# SDRAM.net
KiCad netlist of a schematic drawn in Altium Designer
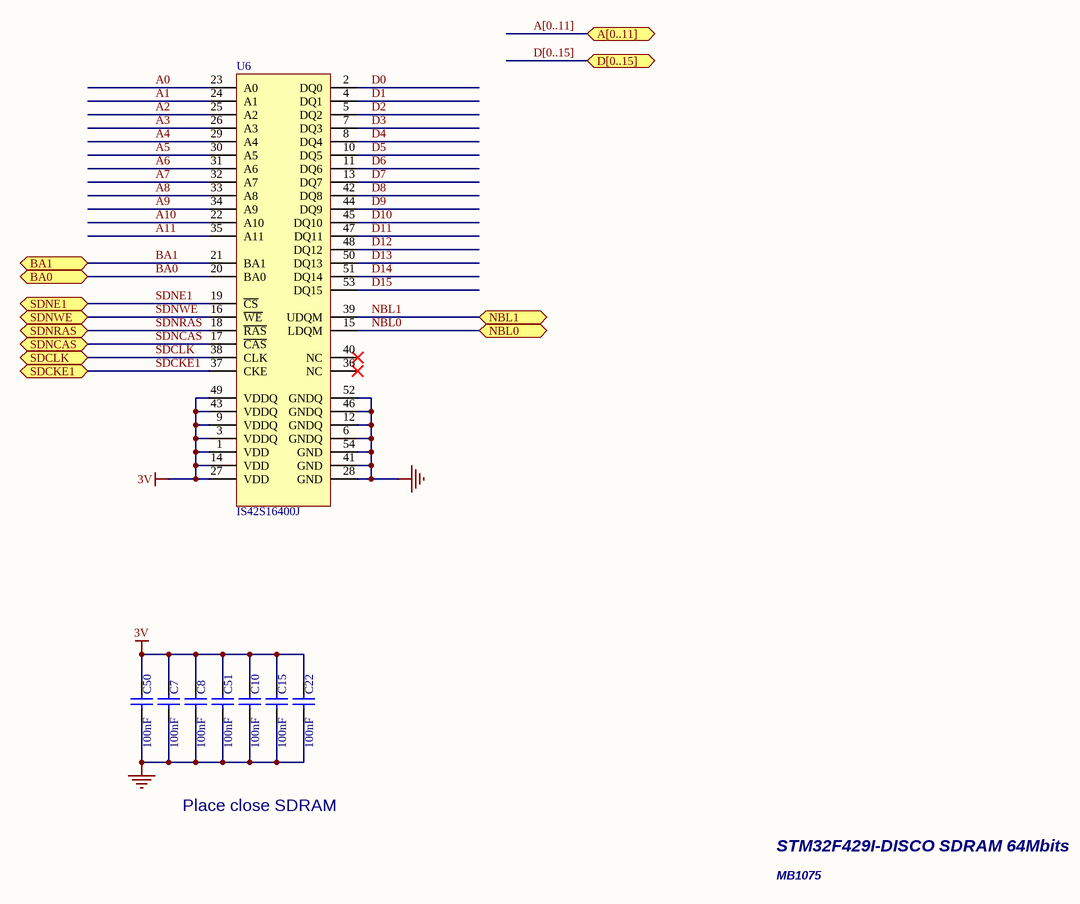
[diagram p0: SDRAM.SchDoc]

(export (version "E")
  (design (tool "Eeschema 10.0.6"))
  (components
    (comp (ref "C7")
      (value "100nF")
      (footprint "0402C")
      (description "Capacitor 0402 / 0603 / 0805")
      (libsource (lib "MCD_TOOLS") (part "Capacitor_ST"))
    )
    (comp (ref "C8")
      (value "100nF")
      (footprint "0402C")
      (description "Capacitor 0402 / 0603 / 0805")
      (libsource (lib "MCD_TOOLS") (part "Capacitor_ST"))
    )
    (comp (ref "C10")
      (value "100nF")
      (footprint "0402C")
      (description "Capacitor 0402 / 0603 / 0805")
      (libsource (lib "MCD_TOOLS") (part "Capacitor_ST"))
    )
    (comp (ref "C15")
      (value "100nF")
      (footprint "0402C")
      (description "Capacitor 0402 / 0603 / 0805")
      (libsource (lib "MCD_TOOLS") (part "Capacitor_ST"))
    )
    (comp (ref "C22")
      (value "100nF")
      (footprint "0402C")
      (description "Capacitor 0402 / 0603 / 0805")
      (libsource (lib "MCD_TOOLS") (part "Capacitor_ST"))
    )
    (comp (ref "C50")
      (value "100nF")
      (footprint "0402C")
      (description "Capacitor 0402 / 0603 / 0805")
      (libsource (lib "MCD_TOOLS") (part "Capacitor_ST"))
    )
    (comp (ref "C51")
      (value "100nF")
      (footprint "0402C")
      (description "Capacitor 0402 / 0603 / 0805")
      (libsource (lib "MCD_TOOLS") (part "Capacitor_ST"))
    )
    (comp (ref "U6")
      (value "IS42S16400J")
      (footprint "TSOP54-II")
      (description "SYNCHRONOUS DYNAMIC RAM, 1 Meg Bits x 16 Bits x 4 Banks (64-MBIT)")
      (libsource (lib "MCD_TOOLS") (part "IS45S16400J"))
    )
  )
  (nets
    (net (code "1") (name "/A0") (class "Default")
      (node (ref "U6") (pin "23") (pinfunction "A0_23") (pintype "passive"))
    )
    (net (code "2") (name "/A1") (class "Default")
      (node (ref "U6") (pin "24") (pinfunction "A1_24") (pintype "passive"))
    )
    (net (code "3") (name "/A2") (class "Default")
      (node (ref "U6") (pin "25") (pinfunction "A2_25") (pintype "passive"))
    )
    (net (code "4") (name "/A3") (class "Default")
      (node (ref "U6") (pin "26") (pinfunction "A3_26") (pintype "passive"))
    )
    (net (code "5") (name "/A4") (class "Default")
      (node (ref "U6") (pin "29") (pinfunction "A4_29") (pintype "passive"))
    )
    (net (code "6") (name "/A5") (class "Default")
      (node (ref "U6") (pin "30") (pinfunction "A5_30") (pintype "passive"))
    )
    (net (code "7") (name "/A6") (class "Default")
      (node (ref "U6") (pin "31") (pinfunction "A6_31") (pintype "passive"))
    )
    (net (code "8") (name "/A7") (class "Default")
      (node (ref "U6") (pin "32") (pinfunction "A7_32") (pintype "passive"))
    )
    (net (code "9") (name "/A8") (class "Default")
      (node (ref "U6") (pin "33") (pinfunction "A8_33") (pintype "passive"))
    )
    (net (code "10") (name "/A9") (class "Default")
      (node (ref "U6") (pin "34") (pinfunction "A9_34") (pintype "passive"))
    )
    (net (code "11") (name "/A10") (class "Default")
      (node (ref "U6") (pin "22") (pinfunction "A10_22") (pintype "passive"))
    )
    (net (code "12") (name "/A11") (class "Default")
      (node (ref "U6") (pin "35") (pinfunction "A11_35") (pintype "passive"))
    )
    (net (code "14") (name "/BA0") (class "Default")
      (node (ref "U6") (pin "20") (pinfunction "BA0_20") (pintype "passive"))
    )
    (net (code "15") (name "/BA1") (class "Default")
      (node (ref "U6") (pin "21") (pinfunction "BA1_21") (pintype "passive"))
    )
    (net (code "16") (name "/D0") (class "Default")
      (node (ref "U6") (pin "2") (pinfunction "DQ0_2") (pintype "passive"))
    )
    (net (code "17") (name "/D1") (class "Default")
      (node (ref "U6") (pin "4") (pinfunction "DQ1_4") (pintype "passive"))
    )
    (net (code "18") (name "/D2") (class "Default")
      (node (ref "U6") (pin "5") (pinfunction "DQ2_5") (pintype "passive"))
    )
    (net (code "19") (name "/D3") (class "Default")
      (node (ref "U6") (pin "7") (pinfunction "DQ3_7") (pintype "passive"))
    )
    (net (code "20") (name "/D4") (class "Default")
      (node (ref "U6") (pin "8") (pinfunction "DQ4_8") (pintype "passive"))
    )
    (net (code "21") (name "/D5") (class "Default")
      (node (ref "U6") (pin "10") (pinfunction "DQ5_10") (pintype "passive"))
    )
    (net (code "22") (name "/D6") (class "Default")
      (node (ref "U6") (pin "11") (pinfunction "DQ6_11") (pintype "passive"))
    )
    (net (code "23") (name "/D7") (class "Default")
      (node (ref "U6") (pin "13") (pinfunction "DQ7_13") (pintype "passive"))
    )
    (net (code "24") (name "/D8") (class "Default")
      (node (ref "U6") (pin "42") (pinfunction "DQ8_42") (pintype "passive"))
    )
    (net (code "25") (name "/D9") (class "Default")
      (node (ref "U6") (pin "44") (pinfunction "DQ9_44") (pintype "passive"))
    )
    (net (code "26") (name "/D10") (class "Default")
      (node (ref "U6") (pin "45") (pinfunction "DQ10_45") (pintype "passive"))
    )
    (net (code "27") (name "/D11") (class "Default")
      (node (ref "U6") (pin "47") (pinfunction "DQ11_47") (pintype "passive"))
    )
    (net (code "28") (name "/D12") (class "Default")
      (node (ref "U6") (pin "48") (pinfunction "DQ12_48") (pintype "passive"))
    )
    (net (code "29") (name "/D13") (class "Default")
      (node (ref "U6") (pin "50") (pinfunction "DQ13_50") (pintype "passive"))
    )
    (net (code "30") (name "/D14") (class "Default")
      (node (ref "U6") (pin "51") (pinfunction "DQ14_51") (pintype "passive"))
    )
    (net (code "31") (name "/D15") (class "Default")
      (node (ref "U6") (pin "53") (pinfunction "DQ15_53") (pintype "passive"))
    )
    (net (code "33") (name "/NBL0") (class "Default")
      (node (ref "U6") (pin "15") (pinfunction "LDQM_15") (pintype "passive"))
    )
    (net (code "34") (name "/NBL1") (class "Default")
      (node (ref "U6") (pin "39") (pinfunction "UDQM_39") (pintype "passive"))
    )
    (net (code "35") (name "/SDCKE1") (class "Default")
      (node (ref "U6") (pin "37") (pinfunction "CKE_37") (pintype "passive"))
    )
    (net (code "36") (name "/SDCLK") (class "Default")
      (node (ref "U6") (pin "38") (pinfunction "CLK_38") (pintype "passive"))
    )
    (net (code "37") (name "/SDNCAS") (class "Default")
      (node (ref "U6") (pin "17") (pinfunction "~{CAS}_17") (pintype "passive"))
    )
    (net (code "38") (name "/SDNE1") (class "Default")
      (node (ref "U6") (pin "19") (pinfunction "~{CS}_19") (pintype "passive"))
    )
    (net (code "39") (name "/SDNRAS") (class "Default")
      (node (ref "U6") (pin "18") (pinfunction "~{RAS}_18") (pintype "passive"))
    )
    (net (code "40") (name "/SDNWE") (class "Default")
      (node (ref "U6") (pin "16") (pinfunction "~{WE}_16") (pintype "passive"))
    )
    (net (code "41") (name "3V") (class "Default")
      (node (ref "C10") (pin "2") (pinfunction "2_2") (pintype "passive"))
      (node (ref "C15") (pin "2") (pinfunction "2_2") (pintype "passive"))
      (node (ref "C22") (pin "2") (pinfunction "2_2") (pintype "passive"))
      (node (ref "C50") (pin "2") (pinfunction "2_2") (pintype "passive"))
      (node (ref "C51") (pin "2") (pinfunction "2_2") (pintype "passive"))
      (node (ref "C7") (pin "2") (pinfunction "2_2") (pintype "passive"))
      (node (ref "C8") (pin "2") (pinfunction "2_2") (pintype "passive"))
      (node (ref "U6") (pin "1") (pinfunction "VDD_1") (pintype "passive"))
      (node (ref "U6") (pin "14") (pinfunction "VDD_14") (pintype "passive"))
      (node (ref "U6") (pin "27") (pinfunction "VDD_27") (pintype "passive"))
      (node (ref "U6") (pin "3") (pinfunction "VDDQ_3") (pintype "passive"))
      (node (ref "U6") (pin "43") (pinfunction "VDDQ_43") (pintype "passive"))
      (node (ref "U6") (pin "49") (pinfunction "VDDQ_49") (pintype "passive"))
      (node (ref "U6") (pin "9") (pinfunction "VDDQ_9") (pintype "passive"))
    )
    (net (code "42") (name "GND") (class "Default")
      (node (ref "C10") (pin "1") (pinfunction "1_1") (pintype "passive"))
      (node (ref "C15") (pin "1") (pinfunction "1_1") (pintype "passive"))
      (node (ref "C22") (pin "1") (pinfunction "1_1") (pintype "passive"))
      (node (ref "C50") (pin "1") (pinfunction "1_1") (pintype "passive"))
      (node (ref "C51") (pin "1") (pinfunction "1_1") (pintype "passive"))
      (node (ref "C7") (pin "1") (pinfunction "1_1") (pintype "passive"))
      (node (ref "C8") (pin "1") (pinfunction "1_1") (pintype "passive"))
      (node (ref "U6") (pin "12") (pinfunction "GNDQ_12") (pintype "passive"))
      (node (ref "U6") (pin "28") (pinfunction "GND_28") (pintype "passive"))
      (node (ref "U6") (pin "41") (pinfunction "GND_41") (pintype "passive"))
      (node (ref "U6") (pin "46") (pinfunction "GNDQ_46") (pintype "passive"))
      (node (ref "U6") (pin "52") (pinfunction "GNDQ_52") (pintype "passive"))
      (node (ref "U6") (pin "54") (pinfunction "GND_54") (pintype "passive"))
      (node (ref "U6") (pin "6") (pinfunction "GNDQ_6") (pintype "passive"))
    )
    (net (code "43") (name "unconnected-(U6-NC-Pad36)") (class "Default")
      (node (ref "U6") (pin "36") (pinfunction "NC_36") (pintype "passive+no_connect"))
    )
    (net (code "44") (name "unconnected-(U6-NC-Pad40)") (class "Default")
      (node (ref "U6") (pin "40") (pinfunction "NC_40") (pintype "passive+no_connect"))
    )
  )
)
